# connectors.net
KiCad netlist of a schematic drawn in Altium Designer
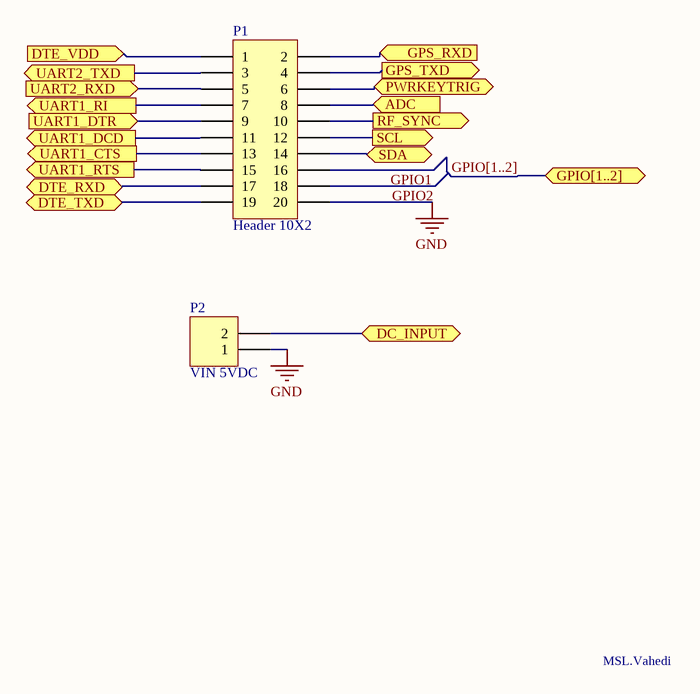
[diagram p0: connectors.SchDoc]

(export (version "E")
  (design (tool "Eeschema 10.0.6"))
  (components
    (comp (ref "P1")
      (value "Header 10X2")
      (footprint "SULIN 20PIN")
      (description "Header, 10-Pin, Dual row")
      (fields (field (name "PUBLISHER") "Altium Limited"))
      (libsource (lib "Miscellaneous Connectors") (part "Header 10X2"))
    )
    (comp (ref "P2")
      (value "VIN 5VDC")
      (footprint "2PIN JACK")
      (description "Header, 2-Pin")
      (fields (field (name "PUBLISHER") "Altium Limited"))
      (libsource (lib "Miscellaneous Connectors") (part "Header 2"))
    )
  )
  (nets
    (net (code "1") (name "/ADC") (class "Default")
      (node (ref "P1") (pin "8") (pinfunction "8_8") (pintype "passive"))
    )
    (net (code "2") (name "/DC_INPUT") (class "Default")
      (node (ref "P2") (pin "2") (pinfunction "2_2") (pintype "passive"))
    )
    (net (code "3") (name "/DTE_RXD") (class "Default")
      (node (ref "P1") (pin "17") (pinfunction "17_17") (pintype "passive"))
    )
    (net (code "4") (name "/DTE_TXD") (class "Default")
      (node (ref "P1") (pin "19") (pinfunction "19_19") (pintype "passive"))
    )
    (net (code "5") (name "/DTE_VDD") (class "Default")
      (node (ref "P1") (pin "1") (pinfunction "1_1") (pintype "passive"))
    )
    (net (code "6") (name "/GPIO1") (class "Default")
      (node (ref "P1") (pin "16") (pinfunction "16_16") (pintype "passive"))
    )
    (net (code "7") (name "/GPIO2") (class "Default")
      (node (ref "P1") (pin "18") (pinfunction "18_18") (pintype "passive"))
    )
    (net (code "9") (name "/GPS_RXD") (class "Default")
      (node (ref "P1") (pin "2") (pinfunction "2_2") (pintype "passive"))
    )
    (net (code "10") (name "/GPS_TXD") (class "Default")
      (node (ref "P1") (pin "4") (pinfunction "4_4") (pintype "passive"))
    )
    (net (code "11") (name "/PWRKEYTRIG") (class "Default")
      (node (ref "P1") (pin "6") (pinfunction "6_6") (pintype "passive"))
    )
    (net (code "12") (name "/RF_SYNC") (class "Default")
      (node (ref "P1") (pin "10") (pinfunction "10_10") (pintype "passive"))
    )
    (net (code "13") (name "/SCL") (class "Default")
      (node (ref "P1") (pin "12") (pinfunction "12_12") (pintype "passive"))
    )
    (net (code "14") (name "/SDA") (class "Default")
      (node (ref "P1") (pin "14") (pinfunction "14_14") (pintype "passive"))
    )
    (net (code "15") (name "/UART1_CTS") (class "Default")
      (node (ref "P1") (pin "13") (pinfunction "13_13") (pintype "passive"))
    )
    (net (code "16") (name "/UART1_DCD") (class "Default")
      (node (ref "P1") (pin "11") (pinfunction "11_11") (pintype "passive"))
    )
    (net (code "17") (name "/UART1_DTR") (class "Default")
      (node (ref "P1") (pin "9") (pinfunction "9_9") (pintype "passive"))
    )
    (net (code "18") (name "/UART1_RI") (class "Default")
      (node (ref "P1") (pin "7") (pinfunction "7_7") (pintype "passive"))
    )
    (net (code "19") (name "/UART1_RTS") (class "Default")
      (node (ref "P1") (pin "15") (pinfunction "15_15") (pintype "passive"))
    )
    (net (code "20") (name "/UART2_RXD") (class "Default")
      (node (ref "P1") (pin "5") (pinfunction "5_5") (pintype "passive"))
    )
    (net (code "21") (name "/UART2_TXD") (class "Default")
      (node (ref "P1") (pin "3") (pinfunction "3_3") (pintype "passive"))
    )
    (net (code "22") (name "GND") (class "Default")
      (node (ref "P1") (pin "20") (pinfunction "20_20") (pintype "passive"))
      (node (ref "P2") (pin "1") (pinfunction "1_1") (pintype "passive"))
    )
  )
)
